# LPCB220_-_CORE_B.net
KiCad netlist of a schematic drawn in Altium Designer
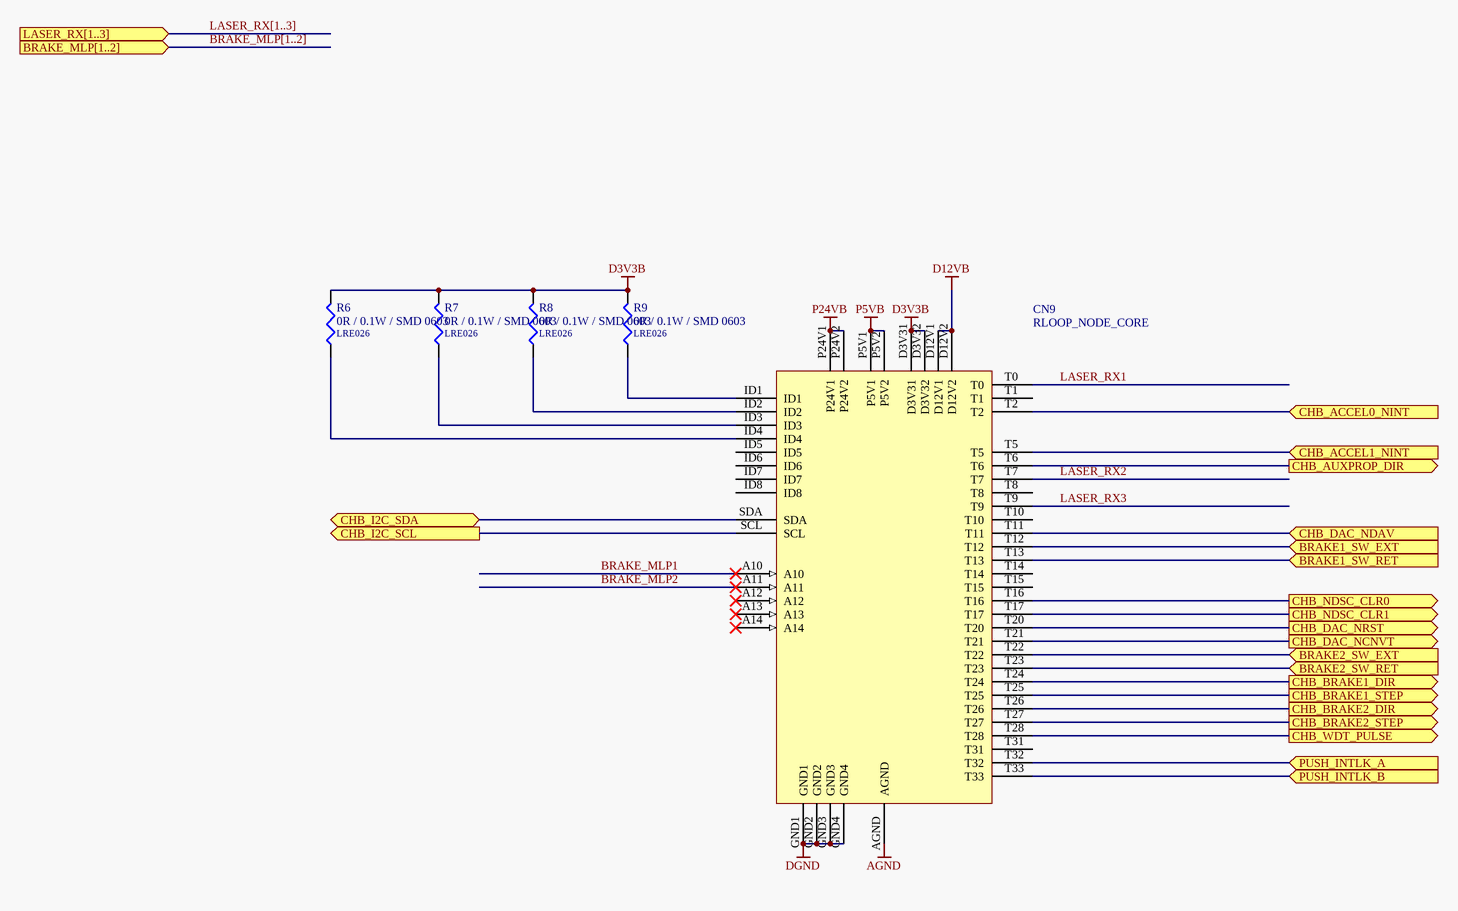
[diagram p0: LPCB220 - CORE B.SchDoc]

(export (version "E")
  (design (tool "Eeschema 10.0.6"))
  (components
    (comp (ref "CN9")
      (value "RLOOP_NODE_CORE")
      (footprint "RLOOP_NODE_CORE")
      (description "rLoop Node Core Connector")
      (libsource (lib "LDL_Connectors") (part "RLOOP_NODE_CORE"))
    )
    (comp (ref "R6")
      (value "0R / 0.1W / SMD 0603")
      (footprint "LFP020__CR1608-0603-IPC7351_B")
      (description "Resistor, Ceramic Chip, 0R, 0.1W, SMD 0603 [LRE026]")
      (fields (field (name "LDL_NUMBER") "LRE026"))
      (libsource (lib "LDL_Resistors") (part "0R / 0.1W / SMD 0603"))
    )
    (comp (ref "R7")
      (value "0R / 0.1W / SMD 0603")
      (footprint "LFP020__CR1608-0603-IPC7351_B")
      (description "Resistor, Ceramic Chip, 0R, 0.1W, SMD 0603 [LRE026]")
      (fields (field (name "LDL_NUMBER") "LRE026"))
      (libsource (lib "LDL_Resistors") (part "0R / 0.1W / SMD 0603"))
    )
    (comp (ref "R8")
      (value "0R / 0.1W / SMD 0603")
      (footprint "LFP020__CR1608-0603-IPC7351_B")
      (description "Resistor, Ceramic Chip, 0R, 0.1W, SMD 0603 [LRE026]")
      (fields (field (name "LDL_NUMBER") "LRE026"))
      (libsource (lib "LDL_Resistors") (part "0R / 0.1W / SMD 0603"))
    )
    (comp (ref "R9")
      (value "0R / 0.1W / SMD 0603")
      (footprint "LFP020__CR1608-0603-IPC7351_B")
      (description "Resistor, Ceramic Chip, 0R, 0.1W, SMD 0603 [LRE026]")
      (fields (field (name "LDL_NUMBER") "LRE026"))
      (libsource (lib "LDL_Resistors") (part "0R / 0.1W / SMD 0603"))
    )
  )
  (nets
    (net (code "1") (name "/BRAKE1_SW_EXT") (class "Default")
      (node (ref "CN9") (pin "T12") (pinfunction "T12_T12") (pintype "passive"))
    )
    (net (code "2") (name "/BRAKE1_SW_RET") (class "Default")
      (node (ref "CN9") (pin "T13") (pinfunction "T13_T13") (pintype "passive"))
    )
    (net (code "3") (name "/BRAKE2_SW_EXT") (class "Default")
      (node (ref "CN9") (pin "T22") (pinfunction "T22_T22") (pintype "passive"))
    )
    (net (code "4") (name "/BRAKE2_SW_RET") (class "Default")
      (node (ref "CN9") (pin "T23") (pinfunction "T23_T23") (pintype "passive"))
    )
    (net (code "5") (name "/BRAKE_MLP1") (class "Default")
      (node (ref "CN9") (pin "A10") (pinfunction "A10_A10") (pintype "input+no_connect"))
    )
    (net (code "6") (name "/BRAKE_MLP2") (class "Default")
      (node (ref "CN9") (pin "A11") (pinfunction "A11_A11") (pintype "input+no_connect"))
    )
    (net (code "8") (name "/CHB_ACCEL0_NINT") (class "Default")
      (node (ref "CN9") (pin "T2") (pinfunction "T2_T2") (pintype "passive"))
    )
    (net (code "9") (name "/CHB_ACCEL1_NINT") (class "Default")
      (node (ref "CN9") (pin "T5") (pinfunction "T5_T5") (pintype "passive"))
    )
    (net (code "10") (name "/CHB_AUXPROP_DIR") (class "Default")
      (node (ref "CN9") (pin "T6") (pinfunction "T6_T6") (pintype "passive"))
    )
    (net (code "11") (name "/CHB_BRAKE1_DIR") (class "Default")
      (node (ref "CN9") (pin "T24") (pinfunction "T24_T24") (pintype "passive"))
    )
    (net (code "12") (name "/CHB_BRAKE1_STEP") (class "Default")
      (node (ref "CN9") (pin "T25") (pinfunction "T25_T25") (pintype "passive"))
    )
    (net (code "13") (name "/CHB_BRAKE2_DIR") (class "Default")
      (node (ref "CN9") (pin "T26") (pinfunction "T26_T26") (pintype "passive"))
    )
    (net (code "14") (name "/CHB_BRAKE2_STEP") (class "Default")
      (node (ref "CN9") (pin "T27") (pinfunction "T27_T27") (pintype "passive"))
    )
    (net (code "15") (name "/CHB_DAC_NCNVT") (class "Default")
      (node (ref "CN9") (pin "T21") (pinfunction "T21_T21") (pintype "passive"))
    )
    (net (code "16") (name "/CHB_DAC_NDAV") (class "Default")
      (node (ref "CN9") (pin "T11") (pinfunction "T11_T11") (pintype "passive"))
    )
    (net (code "17") (name "/CHB_DAC_NRST") (class "Default")
      (node (ref "CN9") (pin "T20") (pinfunction "T20_T20") (pintype "passive"))
    )
    (net (code "18") (name "/CHB_I2C_SCL") (class "Default")
      (node (ref "CN9") (pin "SCL") (pinfunction "SCL_SCL") (pintype "passive"))
    )
    (net (code "19") (name "/CHB_I2C_SDA") (class "Default")
      (node (ref "CN9") (pin "SDA") (pinfunction "SDA_SDA") (pintype "passive"))
    )
    (net (code "20") (name "/CHB_NDSC_CLR0") (class "Default")
      (node (ref "CN9") (pin "T16") (pinfunction "T16_T16") (pintype "passive"))
    )
    (net (code "21") (name "/CHB_NDSC_CLR1") (class "Default")
      (node (ref "CN9") (pin "T17") (pinfunction "T17_T17") (pintype "passive"))
    )
    (net (code "22") (name "/CHB_WDT_PULSE") (class "Default")
      (node (ref "CN9") (pin "T28") (pinfunction "T28_T28") (pintype "passive"))
    )
    (net (code "23") (name "/LASER_RX1") (class "Default")
      (node (ref "CN9") (pin "T0") (pinfunction "T0_T0") (pintype "passive"))
    )
    (net (code "24") (name "/LASER_RX2") (class "Default")
      (node (ref "CN9") (pin "T7") (pinfunction "T7_T7") (pintype "passive"))
    )
    (net (code "25") (name "/LASER_RX3") (class "Default")
      (node (ref "CN9") (pin "T9") (pinfunction "T9_T9") (pintype "passive"))
    )
    (net (code "27") (name "/PUSH_INTLK_A") (class "Default")
      (node (ref "CN9") (pin "T32") (pinfunction "T32_T32") (pintype "passive"))
    )
    (net (code "28") (name "/PUSH_INTLK_B") (class "Default")
      (node (ref "CN9") (pin "T33") (pinfunction "T33_T33") (pintype "passive"))
    )
    (net (code "29") (name "AGND") (class "Default")
      (node (ref "CN9") (pin "AGND") (pinfunction "AGND_AGND") (pintype "power_in"))
    )
    (net (code "30") (name "D3V3B") (class "Default")
      (node (ref "CN9") (pin "D3V31") (pinfunction "D3V31_D3V31") (pintype "power_in"))
      (node (ref "CN9") (pin "D3V32") (pinfunction "D3V32_D3V32") (pintype "power_in"))
      (node (ref "R6") (pin "2") (pintype "passive"))
      (node (ref "R7") (pin "2") (pintype "passive"))
      (node (ref "R8") (pin "2") (pintype "passive"))
      (node (ref "R9") (pin "2") (pintype "passive"))
    )
    (net (code "31") (name "D12VB") (class "Default")
      (node (ref "CN9") (pin "D12V1") (pinfunction "D12V1_D12V1") (pintype "power_in"))
      (node (ref "CN9") (pin "D12V2") (pinfunction "D12V2_D12V2") (pintype "power_in"))
    )
    (net (code "32") (name "DGND") (class "Default")
      (node (ref "CN9") (pin "GND1") (pinfunction "GND1_GND1") (pintype "power_in"))
      (node (ref "CN9") (pin "GND2") (pinfunction "GND2_GND2") (pintype "power_in"))
      (node (ref "CN9") (pin "GND3") (pinfunction "GND3_GND3") (pintype "power_in"))
      (node (ref "CN9") (pin "GND4") (pinfunction "GND4_GND4") (pintype "power_in"))
    )
    (net (code "33") (name "Net-(CN9-PadID1)") (class "Default")
      (node (ref "CN9") (pin "ID1") (pinfunction "ID1_ID1") (pintype "passive"))
      (node (ref "R9") (pin "1") (pintype "passive"))
    )
    (net (code "34") (name "Net-(CN9-PadID2)") (class "Default")
      (node (ref "CN9") (pin "ID2") (pinfunction "ID2_ID2") (pintype "passive"))
      (node (ref "R8") (pin "1") (pintype "passive"))
    )
    (net (code "35") (name "Net-(CN9-PadID3)") (class "Default")
      (node (ref "CN9") (pin "ID3") (pinfunction "ID3_ID3") (pintype "passive"))
      (node (ref "R7") (pin "1") (pintype "passive"))
    )
    (net (code "36") (name "Net-(CN9-PadID4)") (class "Default")
      (node (ref "CN9") (pin "ID4") (pinfunction "ID4_ID4") (pintype "passive"))
      (node (ref "R6") (pin "1") (pintype "passive"))
    )
    (net (code "37") (name "P5VB") (class "Default")
      (node (ref "CN9") (pin "P5V1") (pinfunction "P5V1_P5V1") (pintype "power_in"))
      (node (ref "CN9") (pin "P5V2") (pinfunction "P5V2_P5V2") (pintype "power_in"))
    )
    (net (code "38") (name "P24VB") (class "Default")
      (node (ref "CN9") (pin "P24V1") (pinfunction "P24V1_P24V1") (pintype "power_in"))
      (node (ref "CN9") (pin "P24V2") (pinfunction "P24V2_P24V2") (pintype "power_in"))
    )
    (net (code "39") (name "unconnected-(CN9-PadA12)") (class "Default")
      (node (ref "CN9") (pin "A12") (pinfunction "A12_A12") (pintype "input+no_connect"))
    )
    (net (code "40") (name "unconnected-(CN9-PadA13)") (class "Default")
      (node (ref "CN9") (pin "A13") (pinfunction "A13_A13") (pintype "input+no_connect"))
    )
    (net (code "41") (name "unconnected-(CN9-PadA14)") (class "Default")
      (node (ref "CN9") (pin "A14") (pinfunction "A14_A14") (pintype "input+no_connect"))
    )
    (net (code "42") (name "unconnected-(CN9-PadID5)") (class "Default")
      (node (ref "CN9") (pin "ID5") (pinfunction "ID5_ID5") (pintype "passive"))
    )
    (net (code "43") (name "unconnected-(CN9-PadID6)") (class "Default")
      (node (ref "CN9") (pin "ID6") (pinfunction "ID6_ID6") (pintype "passive"))
    )
    (net (code "44") (name "unconnected-(CN9-PadID7)") (class "Default")
      (node (ref "CN9") (pin "ID7") (pinfunction "ID7_ID7") (pintype "passive"))
    )
    (net (code "45") (name "unconnected-(CN9-PadID8)") (class "Default")
      (node (ref "CN9") (pin "ID8") (pinfunction "ID8_ID8") (pintype "passive"))
    )
    (net (code "46") (name "unconnected-(CN9-PadT1)") (class "Default")
      (node (ref "CN9") (pin "T1") (pinfunction "T1_T1") (pintype "passive"))
    )
    (net (code "47") (name "unconnected-(CN9-PadT8)") (class "Default")
      (node (ref "CN9") (pin "T8") (pinfunction "T8_T8") (pintype "passive"))
    )
    (net (code "48") (name "unconnected-(CN9-PadT10)") (class "Default")
      (node (ref "CN9") (pin "T10") (pinfunction "T10_T10") (pintype "passive"))
    )
    (net (code "49") (name "unconnected-(CN9-PadT14)") (class "Default")
      (node (ref "CN9") (pin "T14") (pinfunction "T14_T14") (pintype "passive"))
    )
    (net (code "50") (name "unconnected-(CN9-PadT15)") (class "Default")
      (node (ref "CN9") (pin "T15") (pinfunction "T15_T15") (pintype "passive"))
    )
    (net (code "51") (name "unconnected-(CN9-PadT31)") (class "Default")
      (node (ref "CN9") (pin "T31") (pinfunction "T31_T31") (pintype "passive"))
    )
  )
)
